# mobile_detector_new.net
KiCad netlist of a schematic drawn in EasyEDA Pro
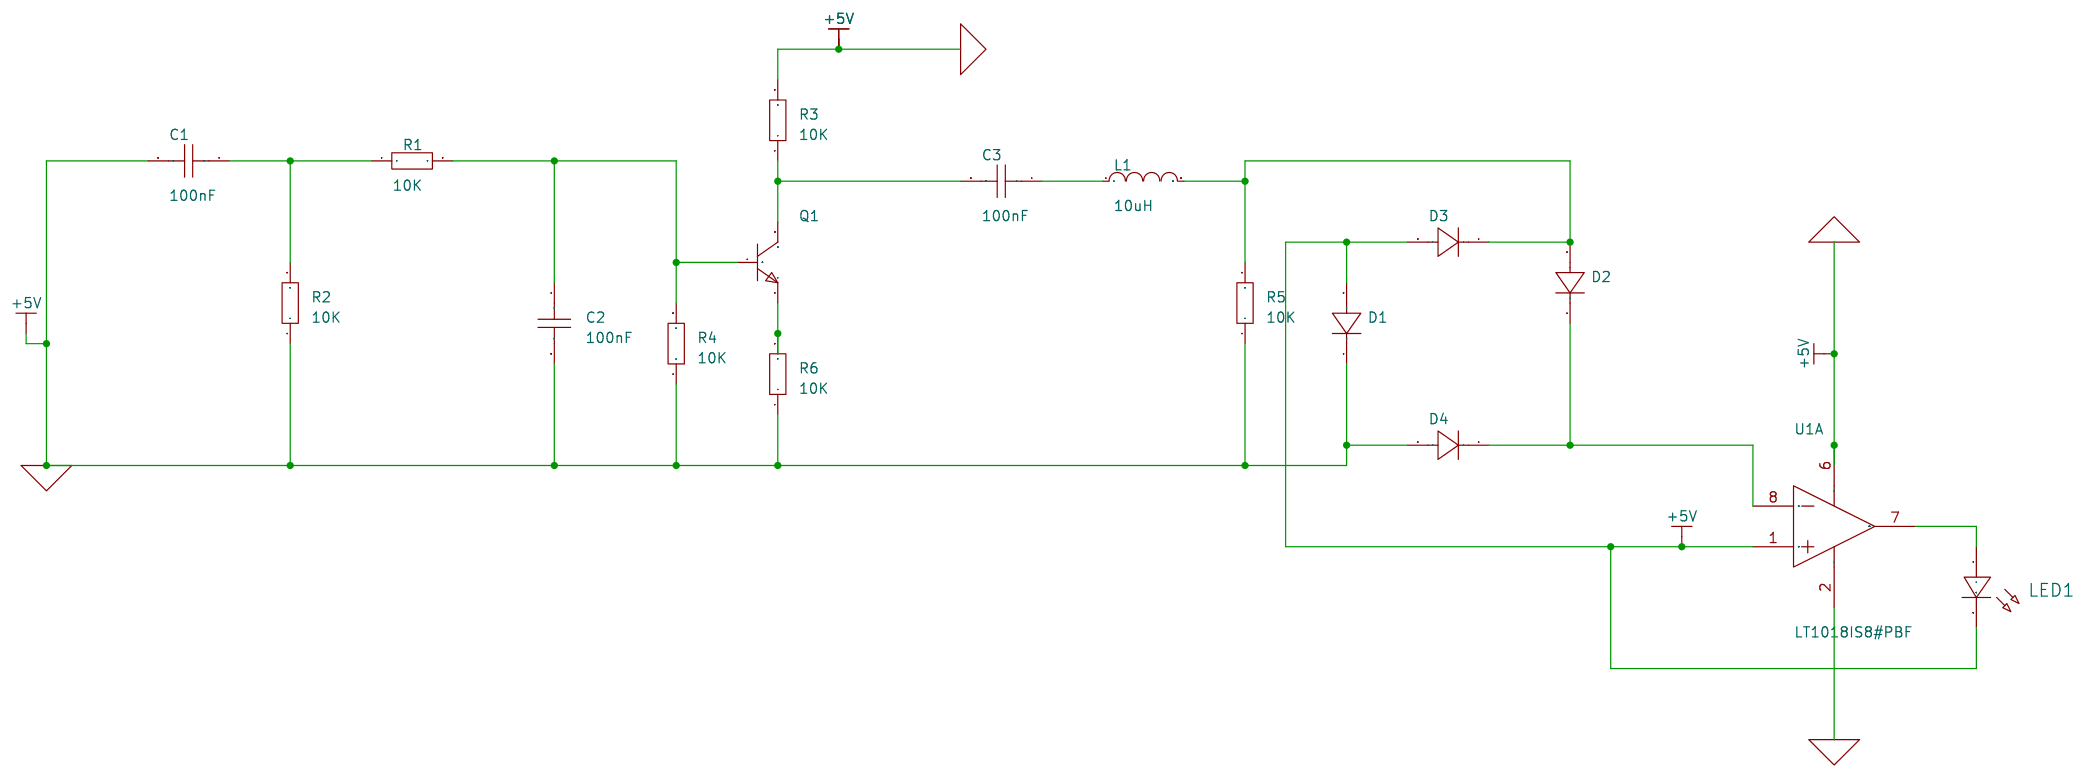
[diagram p0: schematic sheet]

(export (version "E")
  (design (tool "Eeschema 10.0.6"))
  (components
    (comp (ref "C1")
      (value "100nF")
      (footprint "easyedapro:C0603")
      (libsource (lib "easyedapro") (part "CAP"))
    )
    (comp (ref "C2")
      (value "100nF")
      (footprint "easyedapro:C0603")
      (libsource (lib "easyedapro") (part "CAP"))
    )
    (comp (ref "C3")
      (value "100nF")
      (footprint "easyedapro:C0603")
      (libsource (lib "easyedapro") (part "CAP"))
    )
    (comp (ref "D1")
      (value "~")
      (footprint "easyedapro:DO-41_BD2.4-L4.7-P8.70-D0.9-RD")
      (libsource (lib "easyedapro") (part "D_1N4007"))
    )
    (comp (ref "D2")
      (value "~")
      (footprint "easyedapro:DO-41_BD2.4-L4.7-P8.70-D0.9-RD")
      (libsource (lib "easyedapro") (part "D_1N4007"))
    )
    (comp (ref "D3")
      (value "~")
      (footprint "easyedapro:DO-41_BD2.4-L4.7-P8.70-D0.9-RD")
      (libsource (lib "easyedapro") (part "D_1N4007"))
    )
    (comp (ref "D4")
      (value "~")
      (footprint "easyedapro:DO-41_BD2.4-L4.7-P8.70-D0.9-RD")
      (libsource (lib "easyedapro") (part "D_1N4007"))
    )
    (comp (ref "L1") (value "10uH") (footprint "easyedapro:L0402") (libsource (lib "easyedapro") (part "电感")))
    (comp (ref "LED1")
      (value "~")
      (footprint "easyedapro:LED0402-RD_YELLOW")
      (libsource (lib "easyedapro") (part "LED_R"))
    )
    (comp (ref "Q1")
      (value "~")
      (footprint "easyedapro:SOT-23_L2.9-W1.3-P1.90-LS2.4-BR")
      (libsource (lib "easyedapro") (part "NPN"))
    )
    (comp (ref "R1") (value "10K") (footprint "easyedapro:R0603") (libsource (lib "easyedapro") (part "Res")))
    (comp (ref "R2") (value "10K") (footprint "easyedapro:R0603") (libsource (lib "easyedapro") (part "Res")))
    (comp (ref "R3") (value "10K") (footprint "easyedapro:R0603") (libsource (lib "easyedapro") (part "Res")))
    (comp (ref "R4") (value "10K") (footprint "easyedapro:R0603") (libsource (lib "easyedapro") (part "Res")))
    (comp (ref "R5") (value "10K") (footprint "easyedapro:R0603") (libsource (lib "easyedapro") (part "Res")))
    (comp (ref "R6") (value "10K") (footprint "easyedapro:R0603") (libsource (lib "easyedapro") (part "Res")))
    (comp (ref "U1")
      (value "LT1018IS8#PBF")
      (footprint "easyedapro:SO-8_L4.9-W3.9-P1.27-LS5.9-BL")
      (fields (field (name "Manufacturer") "ADI(亚德诺)"))
      (libsource (lib "easyedapro") (part "LT1018IS8#PBF"))
    )
  )
  (nets
    (net (code "1") (name "+5V") (class "Default")
      (node (ref "C1") (pin "2") (pinfunction "2_2") (pintype "input"))
      (node (ref "C2") (pin "2") (pinfunction "2_2") (pintype "input"))
      (node (ref "D1") (pin "1") (pinfunction "K_1") (pintype "input"))
      (node (ref "D1") (pin "2") (pinfunction "A_2") (pintype "input"))
      (node (ref "D3") (pin "2") (pinfunction "A_2") (pintype "input"))
      (node (ref "D4") (pin "2") (pinfunction "A_2") (pintype "input"))
      (node (ref "LED1") (pin "2") (pinfunction "C_2") (pintype "input"))
      (node (ref "R2") (pin "1") (pinfunction "1_1") (pintype "input"))
      (node (ref "R3") (pin "2") (pinfunction "2_2") (pintype "input"))
      (node (ref "R4") (pin "1") (pinfunction "1_1") (pintype "input"))
      (node (ref "R5") (pin "1") (pinfunction "1_1") (pintype "input"))
      (node (ref "R6") (pin "1") (pinfunction "1_1") (pintype "input"))
      (node (ref "U1") (pin "1") (pinfunction "INA+_1") (pintype "unspecified"))
      (node (ref "U1") (pin "6") (pinfunction "V+_6") (pintype "unspecified"))
    )
    (net (code "2") (name "0") (class "Default")
      (node (ref "U1") (pin "2") (pinfunction "V-_2") (pintype "unspecified"))
    )
    (net (code "3") (name "Net-(C1-Pad1)") (class "Default")
      (node (ref "C1") (pin "1") (pinfunction "1_1") (pintype "input"))
      (node (ref "R1") (pin "1") (pinfunction "1_1") (pintype "input"))
      (node (ref "R2") (pin "2") (pinfunction "2_2") (pintype "input"))
    )
    (net (code "4") (name "Net-(C3-Pad1)") (class "Default")
      (node (ref "C3") (pin "1") (pinfunction "1_1") (pintype "input"))
      (node (ref "L1") (pin "1") (pinfunction "1_1") (pintype "input"))
    )
    (net (code "5") (name "Net-(D2-A)") (class "Default")
      (node (ref "D2") (pin "2") (pinfunction "A_2") (pintype "input"))
      (node (ref "D3") (pin "1") (pinfunction "K_1") (pintype "input"))
      (node (ref "L1") (pin "2") (pinfunction "2_2") (pintype "input"))
      (node (ref "R5") (pin "2") (pinfunction "2_2") (pintype "input"))
    )
    (net (code "6") (name "Net-(D2-K)") (class "Default")
      (node (ref "D2") (pin "1") (pinfunction "K_1") (pintype "input"))
      (node (ref "D4") (pin "1") (pinfunction "K_1") (pintype "input"))
      (node (ref "U1") (pin "8") (pinfunction "INA-_8") (pintype "unspecified"))
    )
    (net (code "7") (name "Net-(LED1-A)") (class "Default")
      (node (ref "LED1") (pin "1") (pinfunction "A_1") (pintype "input"))
      (node (ref "U1") (pin "7") (pinfunction "OUTA_7") (pintype "output"))
    )
    (net (code "8") (name "Net-(Q1-B)") (class "Default")
      (node (ref "C2") (pin "1") (pinfunction "1_1") (pintype "input"))
      (node (ref "Q1") (pin "1") (pinfunction "B_1") (pintype "unspecified"))
      (node (ref "R1") (pin "2") (pinfunction "2_2") (pintype "input"))
      (node (ref "R4") (pin "2") (pinfunction "2_2") (pintype "input"))
    )
    (net (code "9") (name "Net-(Q1-C)") (class "Default")
      (node (ref "C3") (pin "2") (pinfunction "2_2") (pintype "input"))
      (node (ref "Q1") (pin "3") (pinfunction "C_3") (pintype "unspecified"))
      (node (ref "R3") (pin "1") (pinfunction "1_1") (pintype "input"))
    )
    (net (code "10") (name "Net-(Q1-E)") (class "Default")
      (node (ref "Q1") (pin "2") (pinfunction "E_2") (pintype "unspecified"))
      (node (ref "R6") (pin "2") (pinfunction "2_2") (pintype "input"))
    )
  )
)
